# MacawBlue_Thing_Plus.net
KiCad netlist of a schematic drawn in EAGLE
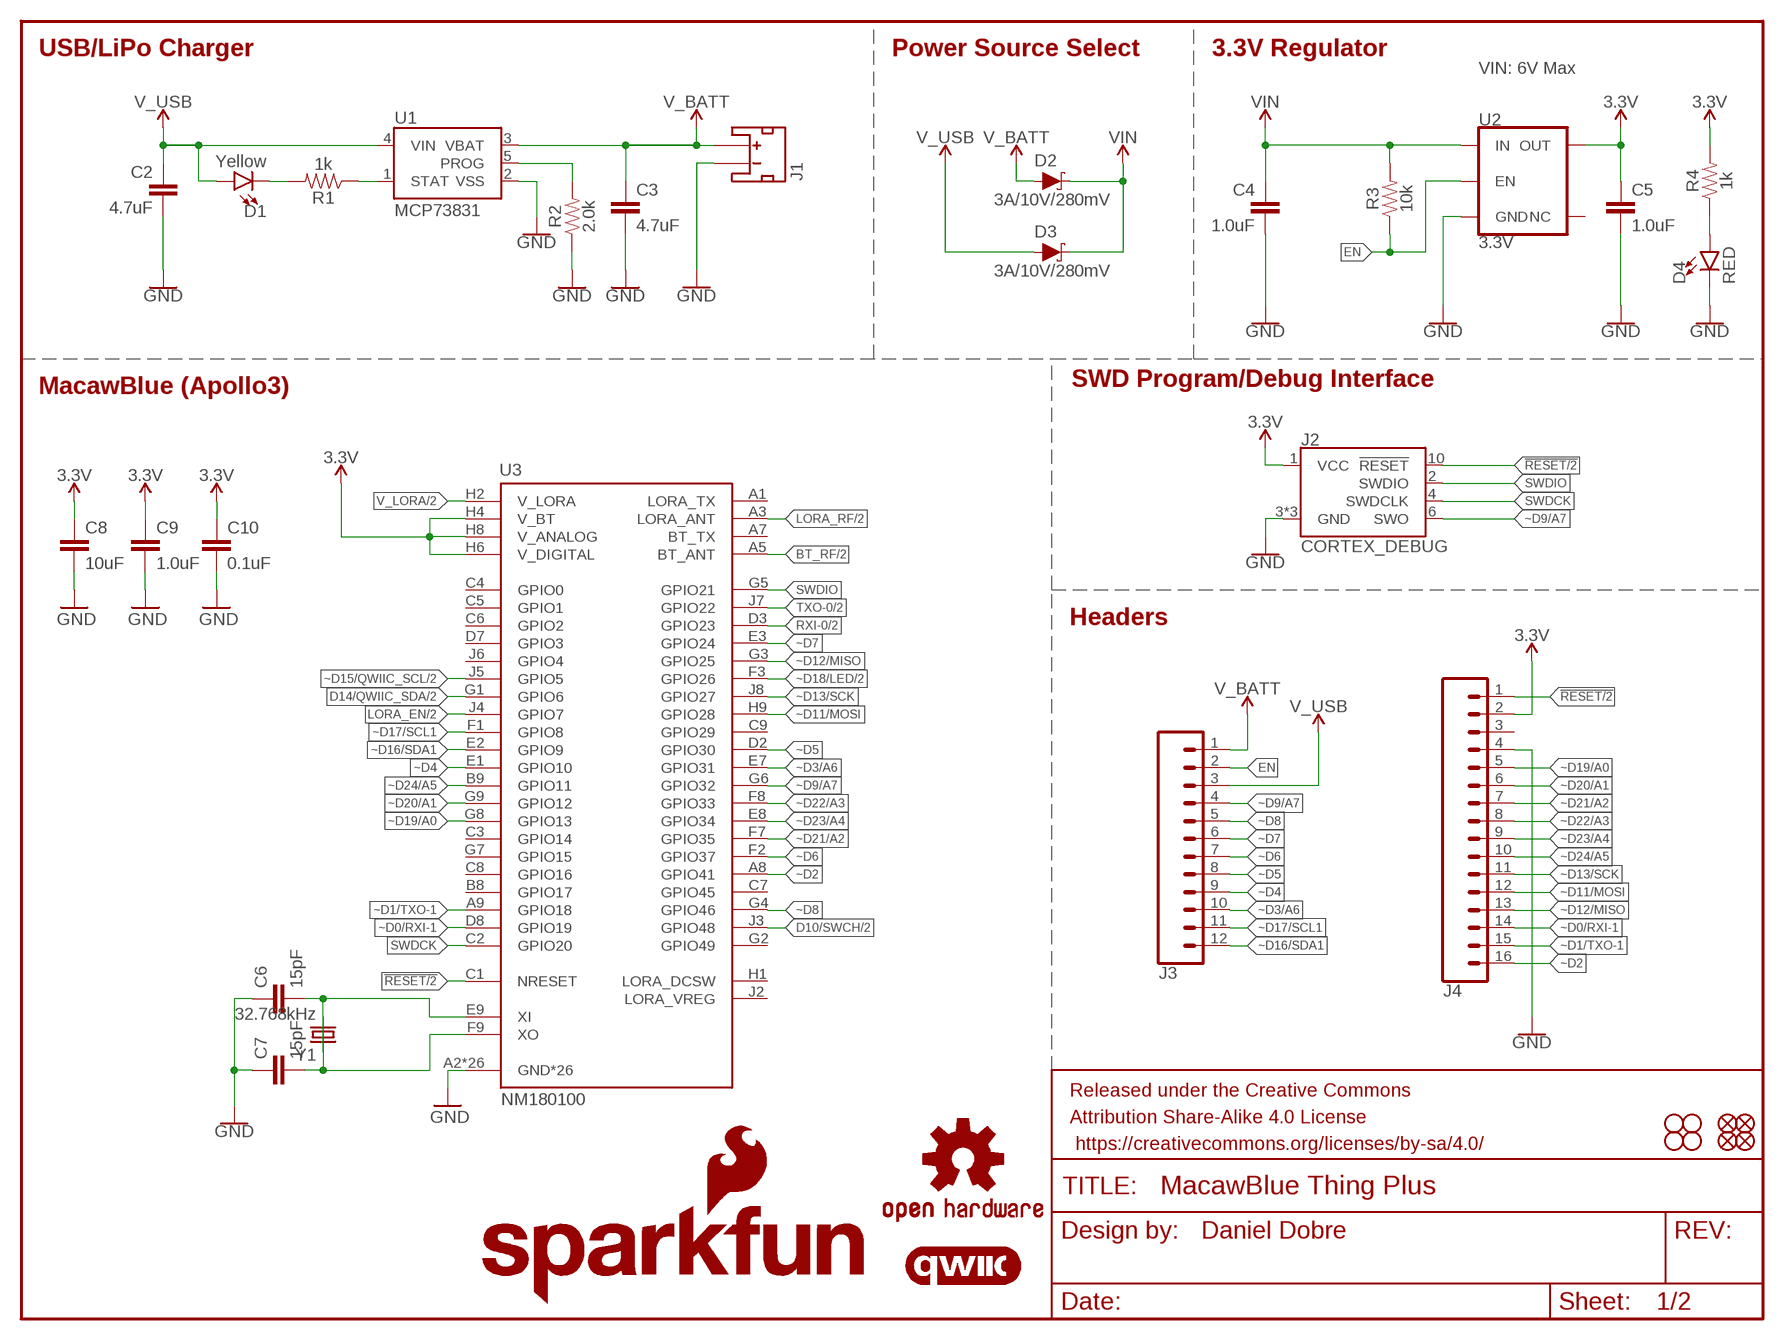
[diagram p0: schematic, sheet 1]
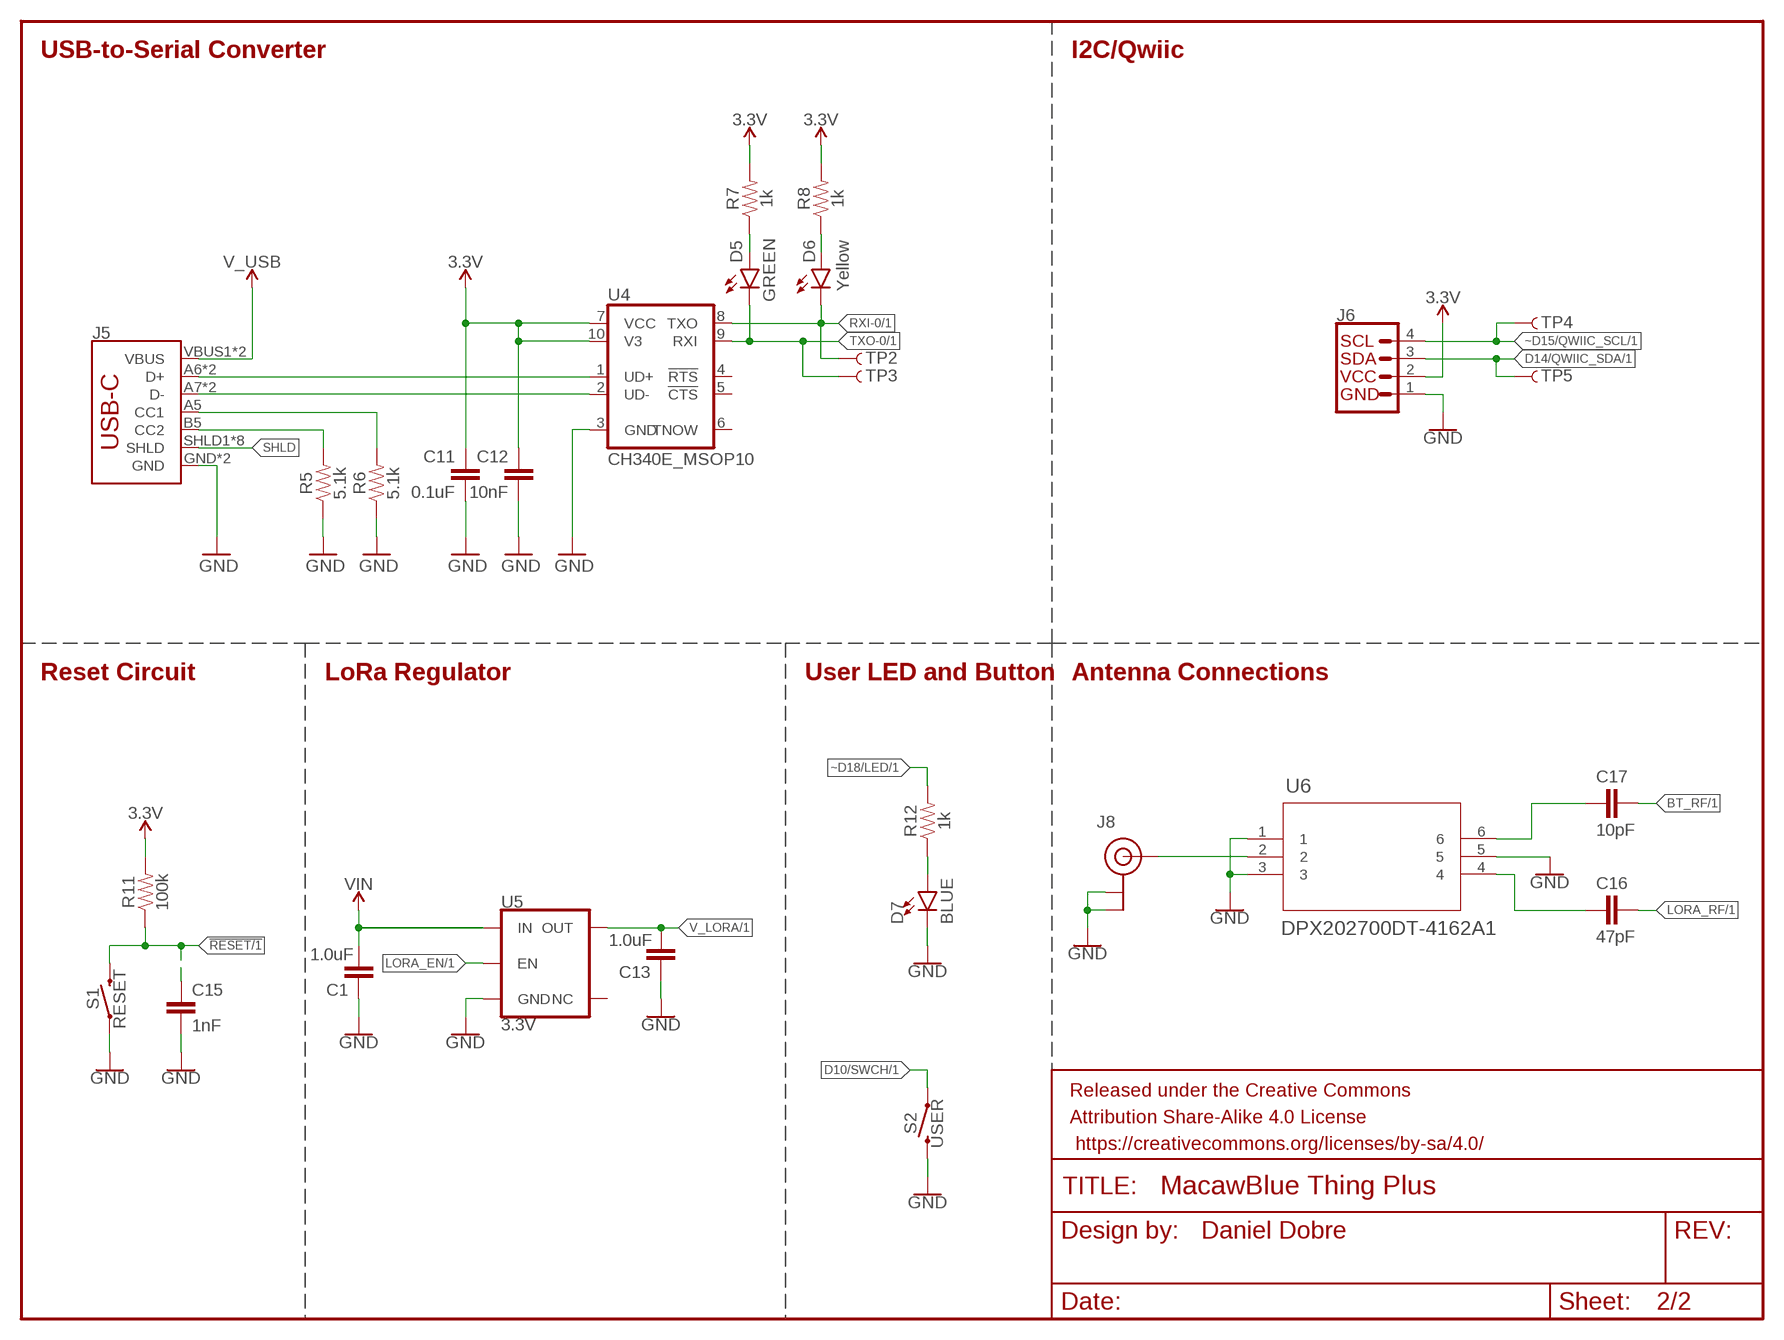
[diagram p1: schematic, sheet 2]

(export (version "E")
  (design (tool "Eeschema 10.0.6"))
  (components
    (comp (ref "C1")
      (value "1.0uF")
      (footprint "eagle-import:0402-TIGHT")
      (libsource (lib "eagle-import") (part "1.0UF-0402T-16V-10%"))
    )
    (comp (ref "C11")
      (value "0.1uF")
      (footprint "eagle-import:0603")
      (libsource (lib "eagle-import") (part "0.1UF-0603-25V-(+80/-20%)"))
    )
    (comp (ref "C12")
      (value "10nF")
      (footprint "eagle-import:0603")
      (libsource (lib "eagle-import") (part "10NF-0603-50V-10%"))
    )
    (comp (ref "C13")
      (value "1.0uF")
      (footprint "eagle-import:0402-TIGHT")
      (libsource (lib "eagle-import") (part "1.0UF-0402T-16V-10%"))
    )
    (comp (ref "C15")
      (value "1nF")
      (footprint "eagle-import:0603")
      (libsource (lib "eagle-import") (part "1.0NF/1000PF-0603-50V-10%"))
    )
    (comp (ref "C16")
      (value "47pF")
      (footprint "eagle-import:0603")
      (libsource (lib "eagle-import") (part "47PF-0603-50V-5%"))
    )
    (comp (ref "C17")
      (value "10pF")
      (footprint "eagle-import:0603")
      (libsource (lib "eagle-import") (part "10PF-0603-50V-5%"))
    )
    (comp (ref "D5")
      (value "GREEN")
      (footprint "eagle-import:LED-0603")
      (libsource (lib "eagle-import") (part "LED-GREEN0603"))
    )
    (comp (ref "D6")
      (value "Yellow")
      (footprint "eagle-import:LED-0603")
      (libsource (lib "eagle-import") (part "LED-YELLOW0603"))
    )
    (comp (ref "D7")
      (value "BLUE")
      (footprint "eagle-import:LED-0603")
      (libsource (lib "eagle-import") (part "LED-BLUE0603"))
    )
    (comp (ref "FRAME2")
      (value "FRAME-LETTERNO_PACKAGE")
      (footprint "eagle-import:DUMMY")
      (fields (field (name "DESIGNER") "Nobody"))
      (libsource (lib "eagle-import") (part "FRAME-LETTERNO_PACKAGE"))
    )
    (comp (ref "J5")
      (value "USB-C")
      (footprint "eagle-import:USB-C-16P")
      (libsource (lib "eagle-import") (part "USB_C2-LAYER"))
    )
    (comp (ref "J6")
      (value "QWIIC_CONNECTORJS-1MM")
      (footprint "eagle-import:JST04_1MM_RA")
      (libsource (lib "eagle-import") (part "QWIIC_CONNECTORJS-1MM"))
    )
    (comp (ref "J8")
      (value "U.FL")
      (footprint "eagle-import:U.FL")
      (libsource (lib "eagle-import") (part "U.FL"))
    )
    (comp (ref "R5")
      (value "5.1k")
      (footprint "eagle-import:0603")
      (libsource (lib "eagle-import") (part "5.1KOHM5.1KOHM-0603-1/10W-1%"))
    )
    (comp (ref "R6")
      (value "5.1k")
      (footprint "eagle-import:0603")
      (libsource (lib "eagle-import") (part "5.1KOHM5.1KOHM-0603-1/10W-1%"))
    )
    (comp (ref "R7")
      (value "1k")
      (footprint "eagle-import:0603")
      (libsource (lib "eagle-import") (part "1KOHM-0603-1/10W-1%"))
    )
    (comp (ref "R8")
      (value "1k")
      (footprint "eagle-import:0603")
      (libsource (lib "eagle-import") (part "1KOHM-0603-1/10W-1%"))
    )
    (comp (ref "R11")
      (value "100k")
      (footprint "eagle-import:0603")
      (libsource (lib "eagle-import") (part "100KOHM-0603-1/10W-1%"))
    )
    (comp (ref "R12")
      (value "1k")
      (footprint "eagle-import:0603")
      (libsource (lib "eagle-import") (part "1KOHM-0603-1/10W-1%"))
    )
    (comp (ref "S1")
      (value "RESET")
      (footprint "eagle-import:TACTILE_SWITCH_SMD_4.6X2.8MM")
      (libsource (lib "eagle-import") (part "MOMENTARY-SWITCH-SPST-SMD-4.6X2.8MM"))
    )
    (comp (ref "S2")
      (value "USER")
      (footprint "eagle-import:TACTILE_SWITCH_SMD_4.6X2.8MM")
      (libsource (lib "eagle-import") (part "MOMENTARY-SWITCH-SPST-SMD-4.6X2.8MM"))
    )
    (comp (ref "TP2")
      (value "TEST-POINTTP_15TH_THRU")
      (footprint "eagle-import:TP_15TH")
      (libsource (lib "eagle-import") (part "TEST-POINTTP_15TH_THRU"))
    )
    (comp (ref "TP3")
      (value "TEST-POINTTP_15TH_THRU")
      (footprint "eagle-import:TP_15TH")
      (libsource (lib "eagle-import") (part "TEST-POINTTP_15TH_THRU"))
    )
    (comp (ref "TP4")
      (value "TEST-POINTTP_15TH_THRU")
      (footprint "eagle-import:TP_15TH")
      (libsource (lib "eagle-import") (part "TEST-POINTTP_15TH_THRU"))
    )
    (comp (ref "TP5")
      (value "TEST-POINTTP_15TH_THRU")
      (footprint "eagle-import:TP_15TH")
      (libsource (lib "eagle-import") (part "TEST-POINTTP_15TH_THRU"))
    )
    (comp (ref "U4")
      (value "CH340E_MSOP10")
      (footprint "eagle-import:MSOP10")
      (libsource (lib "eagle-import") (part "CH340E_MSOP10"))
    )
    (comp (ref "U5")
      (value "3.3V")
      (footprint "eagle-import:SOT23-5")
      (libsource (lib "eagle-import") (part "SparkFun-IC-Power_526_V_REG_AP2112K-3.3V"))
    )
    (comp (ref "U6")
      (value "DPX202700DT-4162A1")
      (footprint "eagle-import:RF_4060A1_TDK")
      (fields (field (name "COPYRIGHT") "Copyright (C) 2018 Accelerated Designs. All rights reserved"))
      (libsource (lib "eagle-import") (part "DPX202700DT-4162A1"))
    )
    (comp (ref "C2")
      (value "4.7uF")
      (footprint "eagle-import:0603")
      (libsource (lib "eagle-import") (part "4.7UF-0603-6.3V-(10%)"))
    )
    (comp (ref "C3")
      (value "4.7uF")
      (footprint "eagle-import:0603")
      (libsource (lib "eagle-import") (part "4.7UF-0603-6.3V-(10%)"))
    )
    (comp (ref "C4")
      (value "1.0uF")
      (footprint "eagle-import:0402-TIGHT")
      (libsource (lib "eagle-import") (part "1.0UF-0402T-16V-10%"))
    )
    (comp (ref "C5")
      (value "1.0uF")
      (footprint "eagle-import:0402-TIGHT")
      (libsource (lib "eagle-import") (part "1.0UF-0402T-16V-10%"))
    )
    (comp (ref "C6")
      (value "15pF")
      (footprint "eagle-import:0603")
      (libsource (lib "eagle-import") (part "15PF-0603-50V-5%"))
    )
    (comp (ref "C7")
      (value "15pF")
      (footprint "eagle-import:0603")
      (libsource (lib "eagle-import") (part "15PF-0603-50V-5%"))
    )
    (comp (ref "C8")
      (value "10uF")
      (footprint "eagle-import:0603")
      (libsource (lib "eagle-import") (part "10UF-0603-6.3V-20%"))
    )
    (comp (ref "C9")
      (value "1.0uF")
      (footprint "eagle-import:0603")
      (libsource (lib "eagle-import") (part "1.0UF-0603-16V-10%"))
    )
    (comp (ref "C10")
      (value "0.1uF")
      (footprint "eagle-import:0603")
      (libsource (lib "eagle-import") (part "0.1UF-0603-25V-(+80/-20%)"))
    )
    (comp (ref "D1")
      (value "Yellow")
      (footprint "eagle-import:LED-0603")
      (libsource (lib "eagle-import") (part "LED-YELLOW0603"))
    )
    (comp (ref "D2")
      (value "3A/10V/280mV")
      (footprint "eagle-import:SOD-323")
      (libsource (lib "eagle-import") (part "DIODE-SCHOTTKY-BAT60A"))
    )
    (comp (ref "D3")
      (value "3A/10V/280mV")
      (footprint "eagle-import:SOD-323")
      (libsource (lib "eagle-import") (part "DIODE-SCHOTTKY-BAT60A"))
    )
    (comp (ref "D4")
      (value "RED")
      (footprint "eagle-import:LED-0603")
      (libsource (lib "eagle-import") (part "LED-RED0603"))
    )
    (comp (ref "FD1")
      (value "FIDUCIALUFIDUCIAL")
      (footprint "eagle-import:FIDUCIAL-MICRO")
      (libsource (lib "eagle-import") (part "FIDUCIALUFIDUCIAL"))
    )
    (comp (ref "FD2")
      (value "FIDUCIALUFIDUCIAL")
      (footprint "eagle-import:FIDUCIAL-MICRO")
      (libsource (lib "eagle-import") (part "FIDUCIALUFIDUCIAL"))
    )
    (comp (ref "FD3")
      (value "FIDUCIALUFIDUCIAL")
      (footprint "eagle-import:FIDUCIAL-MICRO")
      (libsource (lib "eagle-import") (part "FIDUCIALUFIDUCIAL"))
    )
    (comp (ref "FD4")
      (value "FIDUCIALUFIDUCIAL")
      (footprint "eagle-import:FIDUCIAL-MICRO")
      (libsource (lib "eagle-import") (part "FIDUCIALUFIDUCIAL"))
    )
    (comp (ref "FRAME1")
      (value "FRAME-LETTER")
      (footprint "eagle-import:CREATIVE_COMMONS")
      (libsource (lib "eagle-import") (part "FRAME-LETTER"))
    )
    (comp (ref "H1")
      (value "STAND-OFF")
      (footprint "eagle-import:STAND-OFF")
      (libsource (lib "eagle-import") (part "STAND-OFF"))
    )
    (comp (ref "H2")
      (value "STAND-OFF")
      (footprint "eagle-import:STAND-OFF")
      (libsource (lib "eagle-import") (part "STAND-OFF"))
    )
    (comp (ref "H3")
      (value "STAND-OFF")
      (footprint "eagle-import:STAND-OFF")
      (libsource (lib "eagle-import") (part "STAND-OFF"))
    )
    (comp (ref "H4")
      (value "STAND-OFF")
      (footprint "eagle-import:STAND-OFF")
      (libsource (lib "eagle-import") (part "STAND-OFF"))
    )
    (comp (ref "J1")
      (value "JST_2MM_MALE")
      (footprint "eagle-import:JST-2-SMD")
      (libsource (lib "eagle-import") (part "JST_2MM_MALE"))
    )
    (comp (ref "J2")
      (value "CORTEX_DEBUG")
      (footprint "eagle-import:2X5-PTH-1.27MM-NO_SILK")
      (libsource (lib "eagle-import") (part "CORTEX_DEBUG_MINIMUM_PTH_NS"))
    )
    (comp (ref "J3")
      (value "CONN_12SM_SQ_NO_SILK")
      (footprint "eagle-import:1X12_SM_SQ_NOSILK")
      (libsource (lib "eagle-import") (part "CONN_12SM_SQ_NO_SILK"))
    )
    (comp (ref "J4")
      (value "CONN_161X16_SM_SQ_NOSILK")
      (footprint "eagle-import:1X16_SM_SQ_NOSILK")
      (libsource (lib "eagle-import") (part "CONN_161X16_SM_SQ_NOSILK"))
    )
    (comp (ref "LOGO1")
      (value "OSHW-LOGOS")
      (footprint "eagle-import:OSHW-LOGO-S")
      (libsource (lib "eagle-import") (part "OSHW-LOGOS"))
    )
    (comp (ref "LOGO2")
      (value "QWIIC_LOGO_5MM")
      (footprint "eagle-import:QWIIC_5MM")
      (libsource (lib "eagle-import") (part "QWIIC_LOGO_5MM"))
    )
    (comp (ref "LOGO3")
      (value "SFE_LOGO_NAME_FLAME.1_INCH")
      (footprint "eagle-import:SFE_LOGO_NAME_FLAME_.1")
      (libsource (lib "eagle-import") (part "SFE_LOGO_NAME_FLAME.1_INCH"))
    )
    (comp (ref "R1")
      (value "1k")
      (footprint "eagle-import:0603")
      (libsource (lib "eagle-import") (part "1KOHM-0603-1/10W-1%"))
    )
    (comp (ref "R2")
      (value "2.0k")
      (footprint "eagle-import:0603")
      (libsource (lib "eagle-import") (part "2.0KOHM-0603-1/10W-5%"))
    )
    (comp (ref "R3")
      (value "10k")
      (footprint "eagle-import:0603")
      (libsource (lib "eagle-import") (part "10KOHM-0603-1/10W-1%"))
    )
    (comp (ref "R4")
      (value "1k")
      (footprint "eagle-import:0603")
      (libsource (lib "eagle-import") (part "1KOHM-0603-1/10W-1%"))
    )
    (comp (ref "U1")
      (value "MCP73831")
      (footprint "eagle-import:SOT23-5")
      (libsource (lib "eagle-import") (part "MCP73831"))
    )
    (comp (ref "U2")
      (value "3.3V")
      (footprint "eagle-import:SOT23-5")
      (libsource (lib "eagle-import") (part "V_REG_AP2112K-3.3V"))
    )
    (comp (ref "U3")
      (value "NM180100")
      (footprint "eagle-import:LGA81")
      (libsource (lib "eagle-import") (part "NM180100"))
    )
    (comp (ref "Y1")
      (value "32.768kHz")
      (footprint "eagle-import:CRYSTAL-SMD-3.2X1.5MM")
      (libsource (lib "eagle-import") (part "CRYSTAL-32.768KHZSMD-3.2X1.5"))
    )
  )
  (nets
    (net (code "1") (name "3.3V") (class "Default")
      (node (ref "C10") (pin "1") (pinfunction "1_1") (pintype "passive"))
      (node (ref "C11") (pin "1") (pinfunction "1_1") (pintype "passive"))
      (node (ref "C12") (pin "1") (pinfunction "1_1") (pintype "passive"))
      (node (ref "C5") (pin "1") (pinfunction "1_1") (pintype "passive"))
      (node (ref "C8") (pin "1") (pinfunction "1_1") (pintype "passive"))
      (node (ref "C9") (pin "1") (pinfunction "1_1") (pintype "passive"))
      (node (ref "J2") (pin "1") (pinfunction "VCC_1") (pintype "bidirectional"))
      (node (ref "J4") (pin "2") (pinfunction "2_2") (pintype "passive"))
      (node (ref "J6") (pin "2") (pinfunction "2_2") (pintype "power_in"))
      (node (ref "R11") (pin "2") (pinfunction "2_2") (pintype "passive"))
      (node (ref "R4") (pin "2") (pinfunction "2_2") (pintype "passive"))
      (node (ref "R7") (pin "2") (pinfunction "2_2") (pintype "passive"))
      (node (ref "R8") (pin "2") (pinfunction "2_2") (pintype "passive"))
      (node (ref "U2") (pin "5") (pinfunction "OUT_5") (pintype "passive"))
      (node (ref "U3") (pin "H4") (pinfunction "V_BT_H4") (pintype "bidirectional"))
      (node (ref "U3") (pin "H6") (pinfunction "V_DIGITAL_H6") (pintype "bidirectional"))
      (node (ref "U3") (pin "H8") (pinfunction "V_ANALOG_H8") (pintype "bidirectional"))
      (node (ref "U4") (pin "10") (pinfunction "V3_10") (pintype "bidirectional"))
      (node (ref "U4") (pin "7") (pinfunction "VCC_7") (pintype "bidirectional"))
    )
    (net (code "2") (name "BT_RF") (class "Default")
      (node (ref "C17") (pin "1") (pinfunction "1_1") (pintype "passive"))
      (node (ref "U3") (pin "A5") (pinfunction "BT_ANT_A5") (pintype "bidirectional"))
    )
    (net (code "3") (name "D10{slash}SWCH") (class "Default")
      (node (ref "S2") (pin "1") (pinfunction "1_1") (pintype "passive"))
      (node (ref "S2") (pin "2") (pinfunction "1_2") (pintype "passive"))
      (node (ref "U3") (pin "J3") (pinfunction "GPIO48_J3") (pintype "bidirectional"))
    )
    (net (code "4") (name "D14{slash}QWIIC_SDA") (class "Default")
      (node (ref "J6") (pin "3") (pinfunction "3_3") (pintype "passive"))
      (node (ref "TP5") (pin "P$1") (pinfunction "1_P$1") (pintype "bidirectional"))
      (node (ref "U3") (pin "G1") (pinfunction "GPIO6_G1") (pintype "bidirectional"))
    )
    (net (code "5") (name "EN") (class "Default")
      (node (ref "J3") (pin "2") (pinfunction "2_2") (pintype "passive"))
      (node (ref "R3") (pin "1") (pinfunction "1_1") (pintype "passive"))
      (node (ref "U2") (pin "3") (pinfunction "EN_3") (pintype "input"))
    )
    (net (code "6") (name "GND") (class "Default")
      (node (ref "C1") (pin "1") (pinfunction "1_1") (pintype "passive"))
      (node (ref "C10") (pin "2") (pinfunction "2_2") (pintype "passive"))
      (node (ref "C11") (pin "2") (pinfunction "2_2") (pintype "passive"))
      (node (ref "C12") (pin "2") (pinfunction "2_2") (pintype "passive"))
      (node (ref "C13") (pin "1") (pinfunction "1_1") (pintype "passive"))
      (node (ref "C15") (pin "2") (pinfunction "2_2") (pintype "passive"))
      (node (ref "C2") (pin "2") (pinfunction "2_2") (pintype "passive"))
      (node (ref "C3") (pin "2") (pinfunction "2_2") (pintype "passive"))
      (node (ref "C4") (pin "2") (pinfunction "2_2") (pintype "passive"))
      (node (ref "C5") (pin "2") (pinfunction "2_2") (pintype "passive"))
      (node (ref "C6") (pin "1") (pinfunction "1_1") (pintype "passive"))
      (node (ref "C7") (pin "1") (pinfunction "1_1") (pintype "passive"))
      (node (ref "C8") (pin "2") (pinfunction "2_2") (pintype "passive"))
      (node (ref "C9") (pin "2") (pinfunction "2_2") (pintype "passive"))
      (node (ref "D4") (pin "C") (pinfunction "C_C") (pintype "passive"))
      (node (ref "D7") (pin "C") (pinfunction "C_C") (pintype "passive"))
      (node (ref "J1") (pin "1") (pinfunction "-_1") (pintype "bidirectional"))
      (node (ref "J2") (pin "3") (pinfunction "GND_3") (pintype "bidirectional"))
      (node (ref "J2") (pin "5") (pinfunction "GND_5") (pintype "bidirectional"))
      (node (ref "J2") (pin "9") (pinfunction "GND_9") (pintype "bidirectional"))
      (node (ref "J4") (pin "4") (pinfunction "4_4") (pintype "passive"))
      (node (ref "J5") (pin "GND") (pinfunction "GND_GND") (pintype "bidirectional"))
      (node (ref "J5") (pin "GND2") (pinfunction "GND_GND2") (pintype "bidirectional"))
      (node (ref "J6") (pin "1") (pinfunction "1_1") (pintype "power_in"))
      (node (ref "J8") (pin "1") (pinfunction "GND_1") (pintype "bidirectional"))
      (node (ref "J8") (pin "2") (pinfunction "GND_2") (pintype "bidirectional"))
      (node (ref "R2") (pin "1") (pinfunction "1_1") (pintype "passive"))
      (node (ref "R5") (pin "1") (pinfunction "1_1") (pintype "passive"))
      (node (ref "R6") (pin "1") (pinfunction "1_1") (pintype "passive"))
      (node (ref "S1") (pin "1") (pinfunction "1_1") (pintype "passive"))
      (node (ref "S1") (pin "2") (pinfunction "1_2") (pintype "passive"))
      (node (ref "S2") (pin "3") (pinfunction "2_3") (pintype "passive"))
      (node (ref "S2") (pin "4") (pinfunction "2_4") (pintype "passive"))
      (node (ref "U1") (pin "2") (pinfunction "VSS_2") (pintype "power_in"))
      (node (ref "U2") (pin "2") (pinfunction "GND_2") (pintype "input"))
      (node (ref "U3") (pin "A2") (pinfunction "GND*26_A2") (pintype "bidirectional"))
      (node (ref "U3") (pin "A4") (pinfunction "GND*26_A4") (pintype "bidirectional"))
      (node (ref "U3") (pin "A6") (pinfunction "GND*26_A6") (pintype "bidirectional"))
      (node (ref "U3") (pin "B1") (pinfunction "GND*26_B1") (pintype "bidirectional"))
      (node (ref "U3") (pin "B2") (pinfunction "GND*26_B2") (pintype "bidirectional"))
      (node (ref "U3") (pin "B3") (pinfunction "GND*26_B3") (pintype "bidirectional"))
      (node (ref "U3") (pin "B4") (pinfunction "GND*26_B4") (pintype "bidirectional"))
      (node (ref "U3") (pin "B5") (pinfunction "GND*26_B5") (pintype "bidirectional"))
      (node (ref "U3") (pin "B6") (pinfunction "GND*26_B6") (pintype "bidirectional"))
      (node (ref "U3") (pin "B7") (pinfunction "GND*26_B7") (pintype "bidirectional"))
      (node (ref "U3") (pin "D1") (pinfunction "GND*26_D1") (pintype "bidirectional"))
      (node (ref "U3") (pin "D4") (pinfunction "GND*26_D4") (pintype "bidirectional"))
      (node (ref "U3") (pin "D5") (pinfunction "GND*26_D5") (pintype "bidirectional"))
      (node (ref "U3") (pin "D6") (pinfunction "GND*26_D6") (pintype "bidirectional"))
      (node (ref "U3") (pin "D9") (pinfunction "GND*26_D9") (pintype "bidirectional"))
      (node (ref "U3") (pin "E4") (pinfunction "GND*26_E4") (pintype "bidirectional"))
      (node (ref "U3") (pin "E5") (pinfunction "GND*26_E5") (pintype "bidirectional"))
      (node (ref "U3") (pin "E6") (pinfunction "GND*26_E6") (pintype "bidirectional"))
      (node (ref "U3") (pin "F4") (pinfunction "GND*26_F4") (pintype "bidirectional"))
      (node (ref "U3") (pin "F5") (pinfunction "GND*26_F5") (pintype "bidirectional"))
      (node (ref "U3") (pin "F6") (pinfunction "GND*26_F6") (pintype "bidirectional"))
      (node (ref "U3") (pin "H3") (pinfunction "GND*26_H3") (pintype "bidirectional"))
      (node (ref "U3") (pin "H5") (pinfunction "GND*26_H5") (pintype "bidirectional"))
      (node (ref "U3") (pin "H7") (pinfunction "GND*26_H7") (pintype "bidirectional"))
      (node (ref "U3") (pin "J1") (pinfunction "GND*26_J1") (pintype "bidirectional"))
      (node (ref "U3") (pin "J9") (pinfunction "GND*26_J9") (pintype "bidirectional"))
      (node (ref "U4") (pin "3") (pinfunction "GND_3") (pintype "bidirectional"))
      (node (ref "U5") (pin "2") (pinfunction "GND_2") (pintype "input"))
      (node (ref "U6") (pin "1") (pinfunction "1_1") (pintype "passive"))
      (node (ref "U6") (pin "3") (pinfunction "3_3") (pintype "passive"))
      (node (ref "U6") (pin "5") (pinfunction "5_5") (pintype "passive"))
    )
    (net (code "7") (name "LORA_EN") (class "Default")
      (node (ref "U3") (pin "J4") (pinfunction "GPIO7_J4") (pintype "bidirectional"))
      (node (ref "U5") (pin "3") (pinfunction "EN_3") (pintype "input"))
    )
    (net (code "8") (name "LORA_RF") (class "Default")
      (node (ref "C16") (pin "1") (pinfunction "1_1") (pintype "passive"))
      (node (ref "U3") (pin "A3") (pinfunction "LORA_ANT_A3") (pintype "bidirectional"))
    )
    (net (code "9") (name "Net-(C16-Pad2)") (class "Default")
      (node (ref "C16") (pin "2") (pinfunction "2_2") (pintype "passive"))
      (node (ref "U6") (pin "4") (pinfunction "4_4") (pintype "passive"))
    )
    (net (code "10") (name "Net-(C17-Pad2)") (class "Default")
      (node (ref "C17") (pin "2") (pinfunction "2_2") (pintype "passive"))
      (node (ref "U6") (pin "6") (pinfunction "6_6") (pintype "passive"))
    )
    (net (code "11") (name "Net-(D1-PadC)") (class "Default")
      (node (ref "D1") (pin "C") (pinfunction "C_C") (pintype "passive"))
      (node (ref "R1") (pin "2") (pinfunction "2_2") (pintype "passive"))
    )
    (net (code "12") (name "Net-(D4-PadA)") (class "Default")
      (node (ref "D4") (pin "A") (pinfunction "A_A") (pintype "passive"))
      (node (ref "R4") (pin "1") (pinfunction "1_1") (pintype "passive"))
    )
    (net (code "13") (name "Net-(D5-PadA)") (class "Default")
      (node (ref "D5") (pin "A") (pinfunction "A_A") (pintype "passive"))
      (node (ref "R7") (pin "1") (pinfunction "1_1") (pintype "passive"))
    )
    (net (code "14") (name "Net-(D6-PadA)") (class "Default")
      (node (ref "D6") (pin "A") (pinfunction "A_A") (pintype "passive"))
      (node (ref "R8") (pin "1") (pinfunction "1_1") (pintype "passive"))
    )
    (net (code "15") (name "Net-(D7-PadA)") (class "Default")
      (node (ref "D7") (pin "A") (pinfunction "A_A") (pintype "passive"))
      (node (ref "R12") (pin "1") (pinfunction "1_1") (pintype "passive"))
    )
    (net (code "16") (name "Net-(J5-CC1)") (class "Default")
      (node (ref "J5") (pin "A5") (pinfunction "CC1_A5") (pintype "bidirectional"))
      (node (ref "R6") (pin "2") (pinfunction "2_2") (pintype "passive"))
    )
    (net (code "17") (name "Net-(J5-CC2)") (class "Default")
      (node (ref "J5") (pin "B5") (pinfunction "CC2_B5") (pintype "bidirectional"))
      (node (ref "R5") (pin "2") (pinfunction "2_2") (pintype "passive"))
    )
    (net (code "18") (name "Net-(J8-SIGNAL)") (class "Default")
      (node (ref "J8") (pin "FEED") (pinfunction "SIGNAL_FEED") (pintype "bidirectional"))
      (node (ref "U6") (pin "2") (pinfunction "2_2") (pintype "passive"))
    )
    (net (code "19") (name "Net-(U1-PROG)") (class "Default")
      (node (ref "R2") (pin "2") (pinfunction "2_2") (pintype "passive"))
      (node (ref "U1") (pin "5") (pinfunction "PROG_5") (pintype "input"))
    )
    (net (code "20") (name "Net-(U1-STAT)") (class "Default")
      (node (ref "R1") (pin "1") (pinfunction "1_1") (pintype "passive"))
      (node (ref "U1") (pin "1") (pinfunction "STAT_1") (pintype "output"))
    )
    (net (code "21") (name "Net-(U3-XI)") (class "Default")
      (node (ref "C6") (pin "2") (pinfunction "2_2") (pintype "passive"))
      (node (ref "U3") (pin "E9") (pinfunction "XI_E9") (pintype "bidirectional"))
      (node (ref "Y1") (pin "P$1") (pinfunction "1_P$1") (pintype "passive"))
    )
    (net (code "22") (name "Net-(U3-XO)") (class "Default")
      (node (ref "C7") (pin "2") (pinfunction "2_2") (pintype "passive"))
      (node (ref "U3") (pin "F9") (pinfunction "XO_F9") (pintype "bidirectional"))
      (node (ref "Y1") (pin "P$2") (pinfunction "2_P$2") (pintype "passive"))
    )
    (net (code "23") (name "Net-(U4-UD+)") (class "Default")
      (node (ref "J5") (pin "A6") (pinfunction "D+_A6") (pintype "bidirectional"))
      (node (ref "J5") (pin "B6") (pinfunction "D+_B6") (pintype "bidirectional"))
      (node (ref "U4") (pin "1") (pinfunction "UD+_1") (pintype "bidirectional"))
    )
    (net (code "24") (name "Net-(U4-UD-)") (class "Default")
      (node (ref "J5") (pin "A7") (pinfunction "D-_A7") (pintype "bidirectional"))
      (node (ref "J5") (pin "B7") (pinfunction "D-_B7") (pintype "bidirectional"))
      (node (ref "U4") (pin "2") (pinfunction "UD-_2") (pintype "bidirectional"))
    )
    (net (code "25") (name "RXI-0") (class "Default")
      (node (ref "D6") (pin "C") (pinfunction "C_C") (pintype "passive"))
      (node (ref "TP2") (pin "P$1") (pinfunction "1_P$1") (pintype "bidirectional"))
      (node (ref "U3") (pin "D3") (pinfunction "GPIO23_D3") (pintype "bidirectional"))
      (node (ref "U4") (pin "8") (pinfunction "TXO_8") (pintype "bidirectional"))
    )
    (net (code "26") (name "SHLD") (class "Default")
      (node (ref "J5") (pin "SHLD1") (pinfunction "SHLD_SHLD1") (pintype "bidirectional"))
      (node (ref "J5") (pin "SHLD2") (pinfunction "SHLD_SHLD2") (pintype "bidirectional"))
      (node (ref "J5") (pin "SHLD3") (pinfunction "SHLD_SHLD3") (pintype "bidirectional"))
      (node (ref "J5") (pin "SHLD4") (pinfunction "SHLD_SHLD4") (pintype "bidirectional"))
      (node (ref "J5") (pin "SHLD5") (pinfunction "SHLD_SHLD5") (pintype "bidirectional"))
      (node (ref "J5") (pin "SHLD6") (pinfunction "SHLD_SHLD6") (pintype "bidirectional"))
      (node (ref "J5") (pin "SHLD7") (pinfunction "SHLD_SHLD7") (pintype "bidirectional"))
      (node (ref "J5") (pin "SHLD8") (pinfunction "SHLD_SHLD8") (pintype "bidirectional"))
    )
    (net (code "27") (name "SWDCK") (class "Default")
      (node (ref "J2") (pin "4") (pinfunction "SWDCLK_4") (pintype "bidirectional"))
      (node (ref "U3") (pin "C2") (pinfunction "GPIO20_C2") (pintype "bidirectional"))
    )
    (net (code "28") (name "SWDIO") (class "Default")
      (node (ref "J2") (pin "2") (pinfunction "SWDIO_2") (pintype "bidirectional"))
      (node (ref "U3") (pin "G5") (pinfunction "GPIO21_G5") (pintype "bidirectional"))
    )
    (net (code "29") (name "TXO-0") (class "Default")
      (node (ref "D5") (pin "C") (pinfunction "C_C") (pintype "passive"))
      (node (ref "TP3") (pin "P$1") (pinfunction "1_P$1") (pintype "bidirectional"))
      (node (ref "U3") (pin "J7") (pinfunction "GPIO22_J7") (pintype "bidirectional"))
      (node (ref "U4") (pin "9") (pinfunction "RXI_9") (pintype "bidirectional"))
    )
    (net (code "30") (name "VIN") (class "Default")
      (node (ref "C1") (pin "2") (pinfunction "2_2") (pintype "passive"))
      (node (ref "C4") (pin "1") (pinfunction "1_1") (pintype "passive"))
      (node (ref "D2") (pin "C") (pinfunction "C_C") (pintype "passive"))
      (node (ref "D3") (pin "C") (pinfunction "C_C") (pintype "passive"))
      (node (ref "R3") (pin "2") (pinfunction "2_2") (pintype "passive"))
      (node (ref "U2") (pin "1") (pinfunction "IN_1") (pintype "input"))
      (node (ref "U5") (pin "1") (pinfunction "IN_1") (pintype "input"))
    )
    (net (code "31") (name "V_BATT") (class "Default")
      (node (ref "C3") (pin "1") (pinfunction "1_1") (pintype "passive"))
      (node (ref "D2") (pin "A") (pinfunction "A_A") (pintype "passive"))
      (node (ref "J1") (pin "2") (pinfunction "+_2") (pintype "bidirectional"))
      (node (ref "J3") (pin "1") (pinfunction "1_1") (pintype "passive"))
      (node (ref "U1") (pin "3") (pinfunction "VBAT_3") (pintype "power_in"))
    )
    (net (code "32") (name "V_LORA") (class "Default")
      (node (ref "C13") (pin "2") (pinfunction "2_2") (pintype "passive"))
      (node (ref "U3") (pin "H2") (pinfunction "V_LORA_H2") (pintype "bidirectional"))
      (node (ref "U5") (pin "5") (pinfunction "OUT_5") (pintype "passive"))
    )
    (net (code "33") (name "V_USB") (class "Default")
      (node (ref "C2") (pin "1") (pinfunction "1_1") (pintype "passive"))
      (node (ref "D1") (pin "A") (pinfunction "A_A") (pintype "passive"))
      (node (ref "D3") (pin "A") (pinfunction "A_A") (pintype "passive"))
      (node (ref "J3") (pin "3") (pinfunction "3_3") (pintype "passive"))
      (node (ref "J5") (pin "VBUS1") (pinfunction "VBUS_VBUS1") (pintype "bidirectional"))
      (node (ref "J5") (pin "VBUS2") (pinfunction "VBUS_VBUS2") (pintype "bidirectional"))
      (node (ref "U1") (pin "4") (pinfunction "VIN_4") (pintype "power_in"))
    )
    (net (code "34") (name "unconnected-(J1-PAD1-PadNC1)") (class "Default")
      (node (ref "J1") (pin "NC1") (pinfunction "PAD1_NC1") (pintype "bidirectional"))
    )
    (net (code "35") (name "unconnected-(J1-PAD2-PadNC2)") (class "Default")
      (node (ref "J1") (pin "NC2") (pinfunction "PAD2_NC2") (pintype "bidirectional"))
    )
    (net (code "36") (name "unconnected-(J4-Pad3)") (class "Default")
      (node (ref "J4") (pin "3") (pinfunction "3_3") (pintype "passive"))
    )
    (net (code "37") (name "unconnected-(U2-NC-Pad4)") (class "Default")
      (node (ref "U2") (pin "4") (pinfunction "NC_4") (pintype "no_connect"))
    )
    (net (code "38") (name "unconnected-(U3-BT_TX-PadA7)") (class "Default")
      (node (ref "U3") (pin "A7") (pinfunction "BT_TX_A7") (pintype "bidirectional"))
    )
    (net (code "39") (name "unconnected-(U3-GPIO0-PadC4)") (class "Default")
      (node (ref "U3") (pin "C4") (pinfunction "GPIO0_C4") (pintype "bidirectional"))
    )
    (net (code "40") (name "unconnected-(U3-GPIO1-PadC5)") (class "Default")
      (node (ref "U3") (pin "C5") (pinfunction "GPIO1_C5") (pintype "bidirectional"))
    )
    (net (code "41") (name "unconnected-(U3-GPIO2-PadC6)") (class "Default")
      (node (ref "U3") (pin "C6") (pinfunction "GPIO2_C6") (pintype "bidirectional"))
    )
    (net (code "42") (name "unconnected-(U3-GPIO3-PadD7)") (class "Default")
      (node (ref "U3") (pin "D7") (pinfunction "GPIO3_D7") (pintype "bidirectional"))
    )
    (net (code "43") (name "unconnected-(U3-GPIO4-PadJ6)") (class "Default")
      (node (ref "U3") (pin "J6") (pinfunction "GPIO4_J6") (pintype "bidirectional"))
    )
    (net (code "44") (name "unconnected-(U3-GPIO14-PadC3)") (class "Default")
      (node (ref "U3") (pin "C3") (pinfunction "GPIO14_C3") (pintype "bidirectional"))
    )
    (net (code "45") (name "unconnected-(U3-GPIO15-PadG7)") (class "Default")
      (node (ref "U3") (pin "G7") (pinfunction "GPIO15_G7") (pintype "bidirectional"))
    )
    (net (code "46") (name "unconnected-(U3-GPIO16-PadC8)") (class "Default")
      (node (ref "U3") (pin "C8") (pinfunction "GPIO16_C8") (pintype "bidirectional"))
    )
    (net (code "47") (name "unconnected-(U3-GPIO17-PadB8)") (class "Default")
      (node (ref "U3") (pin "B8") (pinfunction "GPIO17_B8") (pintype "bidirectional"))
    )
    (net (code "48") (name "unconnected-(U3-GPIO29-PadC9)") (class "Default")
      (node (ref "U3") (pin "C9") (pinfunction "GPIO29_C9") (pintype "bidirectional"))
    )
    (net (code "49") (name "unconnected-(U3-GPIO45-PadC7)") (class "Default")
      (node (ref "U3") (pin "C7") (pinfunction "GPIO45_C7") (pintype "bidirectional"))
    )
    (net (code "50") (name "unconnected-(U3-GPIO49-PadG2)") (class "Default")
      (node (ref "U3") (pin "G2") (pinfunction "GPIO49_G2") (pintype "bidirectional"))
    )
    (net (code "51") (name "unconnected-(U3-LORA_DCSW-PadH1)") (class "Default")
      (node (ref "U3") (pin "H1") (pinfunction "LORA_DCSW_H1") (pintype "bidirectional"))
    )
    (net (code "52") (name "unconnected-(U3-LORA_TX-PadA1)") (class "Default")
      (node (ref "U3") (pin "A1") (pinfunction "LORA_TX_A1") (pintype "bidirectional"))
    )
    (net (code "53") (name "unconnected-(U3-LORA_VREG-PadJ2)") (class "Default")
      (node (ref "U3") (pin "J2") (pinfunction "LORA_VREG_J2") (pintype "bidirectional"))
    )
    (net (code "54") (name "unconnected-(U4-TNOW-Pad6)") (class "Default")
      (node (ref "U4") (pin "6") (pinfunction "TNOW_6") (pintype "bidirectional"))
    )
    (net (code "55") (name "unconnected-(U4-~{CTS}-Pad5)") (class "Default")
      (node (ref "U4") (pin "5") (pinfunction "~{CTS}_5") (pintype "bidirectional"))
    )
    (net (code "56") (name "unconnected-(U4-~{RTS}-Pad4)") (class "Default")
      (node (ref "U4") (pin "4") (pinfunction "~{RTS}_4") (pintype "bidirectional"))
    )
    (net (code "57") (name "unconnected-(U5-NC-Pad4)") (class "Default")
      (node (ref "U5") (pin "4") (pinfunction "NC_4") (pintype "no_connect"))
    )
    (net (code "58") (name "~{D0{slash}RXI-1}") (class "Default")
      (node (ref "J4") (pin "14") (pinfunction "14_14") (pintype "passive"))
      (node (ref "U3") (pin "D8") (pinfunction "GPIO19_D8") (pintype "bidirectional"))
    )
    (net (code "59") (name "~{D1{slash}TXO-1}") (class "Default")
      (node (ref "J4") (pin "15") (pinfunction "15_15") (pintype "passive"))
      (node (ref "U3") (pin "A9") (pinfunction "GPIO18_A9") (pintype "bidirectional"))
    )
    (net (code "60") (name "~{D2}") (class "Default")
      (node (ref "J4") (pin "16") (pinfunction "16_16") (pintype "passive"))
      (node (ref "U3") (pin "A8") (pinfunction "GPIO41_A8") (pintype "bidirectional"))
    )
    (net (code "61") (name "~{D3{slash}A6}") (class "Default")
      (node (ref "J3") (pin "10") (pinfunction "10_10") (pintype "passive"))
      (node (ref "U3") (pin "E7") (pinfunction "GPIO31_E7") (pintype "bidirectional"))
    )
    (net (code "62") (name "~{D4}") (class "Default")
      (node (ref "J3") (pin "9") (pinfunction "9_9") (pintype "passive"))
      (node (ref "U3") (pin "E1") (pinfunction "GPIO10_E1") (pintype "bidirectional"))
    )
    (net (code "63") (name "~{D5}") (class "Default")
      (node (ref "J3") (pin "8") (pinfunction "8_8") (pintype "passive"))
      (node (ref "U3") (pin "D2") (pinfunction "GPIO30_D2") (pintype "bidirectional"))
    )
    (net (code "64") (name "~{D6}") (class "Default")
      (node (ref "J3") (pin "7") (pinfunction "7_7") (pintype "passive"))
      (node (ref "U3") (pin "F2") (pinfunction "GPIO37_F2") (pintype "bidirectional"))
    )
    (net (code "65") (name "~{D7}") (class "Default")
      (node (ref "J3") (pin "6") (pinfunction "6_6") (pintype "passive"))
      (node (ref "U3") (pin "E3") (pinfunction "GPIO24_E3") (pintype "bidirectional"))
    )
    (net (code "66") (name "~{D8}") (class "Default")
      (node (ref "J3") (pin "5") (pinfunction "5_5") (pintype "passive"))
      (node (ref "U3") (pin "G4") (pinfunction "GPIO46_G4") (pintype "bidirectional"))
    )
    (net (code "67") (name "~{D9{slash}A7}") (class "Default")
      (node (ref "J2") (pin "6") (pinfunction "SWO_6") (pintype "bidirectional"))
      (node (ref "J3") (pin "4") (pinfunction "4_4") (pintype "passive"))
      (node (ref "U3") (pin "G6") (pinfunction "GPIO32_G6") (pintype "bidirectional"))
    )
    (net (code "68") (name "~{D11{slash}MOSI}") (class "Default")
      (node (ref "J4") (pin "12") (pinfunction "12_12") (pintype "passive"))
      (node (ref "U3") (pin "H9") (pinfunction "GPIO28_H9") (pintype "bidirectional"))
    )
    (net (code "69") (name "~{D12{slash}MISO}") (class "Default")
      (node (ref "J4") (pin "13") (pinfunction "13_13") (pintype "passive"))
      (node (ref "U3") (pin "G3") (pinfunction "GPIO25_G3") (pintype "bidirectional"))
    )
    (net (code "70") (name "~{D13{slash}SCK}") (class "Default")
      (node (ref "J4") (pin "11") (pinfunction "11_11") (pintype "passive"))
      (node (ref "U3") (pin "J8") (pinfunction "GPIO27_J8") (pintype "bidirectional"))
    )
    (net (code "71") (name "~{D15{slash}QWIIC_SCL}") (class "Default")
      (node (ref "J6") (pin "4") (pinfunction "4_4") (pintype "passive"))
      (node (ref "TP4") (pin "P$1") (pinfunction "1_P$1") (pintype "bidirectional"))
      (node (ref "U3") (pin "J5") (pinfunction "GPIO5_J5") (pintype "bidirectional"))
    )
    (net (code "72") (name "~{D16{slash}SDA1}") (class "Default")
      (node (ref "J3") (pin "12") (pinfunction "12_12") (pintype "passive"))
      (node (ref "U3") (pin "E2") (pinfunction "GPIO9_E2") (pintype "bidirectional"))
    )
    (net (code "73") (name "~{D17{slash}SCL1}") (class "Default")
      (node (ref "J3") (pin "11") (pinfunction "11_11") (pintype "passive"))
      (node (ref "U3") (pin "F1") (pinfunction "GPIO8_F1") (pintype "bidirectional"))
    )
    (net (code "74") (name "~{D18{slash}LED}") (class "Default")
      (node (ref "R12") (pin "2") (pinfunction "2_2") (pintype "passive"))
      (node (ref "U3") (pin "F3") (pinfunction "GPIO26_F3") (pintype "bidirectional"))
    )
    (net (code "75") (name "~{D19{slash}A0}") (class "Default")
      (node (ref "J4") (pin "5") (pinfunction "5_5") (pintype "passive"))
      (node (ref "U3") (pin "G8") (pinfunction "GPIO13_G8") (pintype "bidirectional"))
    )
    (net (code "76") (name "~{D20{slash}A1}") (class "Default")
      (node (ref "J4") (pin "6") (pinfunction "6_6") (pintype "passive"))
      (node (ref "U3") (pin "G9") (pinfunction "GPIO12_G9") (pintype "bidirectional"))
    )
    (net (code "77") (name "~{D21{slash}A2}") (class "Default")
      (node (ref "J4") (pin "7") (pinfunction "7_7") (pintype "passive"))
      (node (ref "U3") (pin "F7") (pinfunction "GPIO35_F7") (pintype "bidirectional"))
    )
    (net (code "78") (name "~{D22{slash}A3}") (class "Default")
      (node (ref "J4") (pin "8") (pinfunction "8_8") (pintype "passive"))
      (node (ref "U3") (pin "F8") (pinfunction "GPIO33_F8") (pintype "bidirectional"))
    )
    (net (code "79") (name "~{D23{slash}A4}") (class "Default")
      (node (ref "J4") (pin "9") (pinfunction "9_9") (pintype "passive"))
      (node (ref "U3") (pin "E8") (pinfunction "GPIO34_E8") (pintype "bidirectional"))
    )
    (net (code "80") (name "~{D24{slash}A5}") (class "Default")
      (node (ref "J4") (pin "10") (pinfunction "10_10") (pintype "passive"))
      (node (ref "U3") (pin "B9") (pinfunction "GPIO11_B9") (pintype "bidirectional"))
    )
    (net (code "81") (name "~{RESET}") (class "Default")
      (node (ref "C15") (pin "1") (pinfunction "1_1") (pintype "passive"))
      (node (ref "J2") (pin "10") (pinfunction "~{RESET}_10") (pintype "bidirectional"))
      (node (ref "J4") (pin "1") (pinfunction "1_1") (pintype "passive"))
      (node (ref "R11") (pin "1") (pinfunction "1_1") (pintype "passive"))
      (node (ref "S1") (pin "3") (pinfunction "2_3") (pintype "passive"))
      (node (ref "S1") (pin "4") (pinfunction "2_4") (pintype "passive"))
      (node (ref "U3") (pin "C1") (pinfunction "NRESET_C1") (pintype "bidirectional"))
    )
  )
)
